# busses.net
KiCad netlist of a schematic drawn in EAGLE
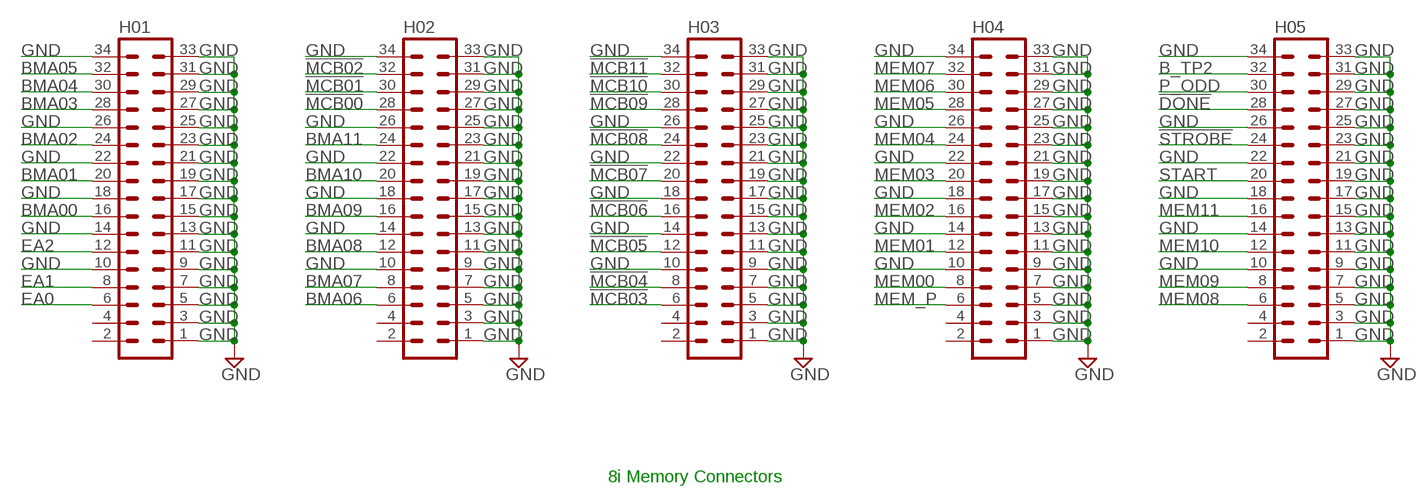
[diagram p0: schematic, sheet 1]
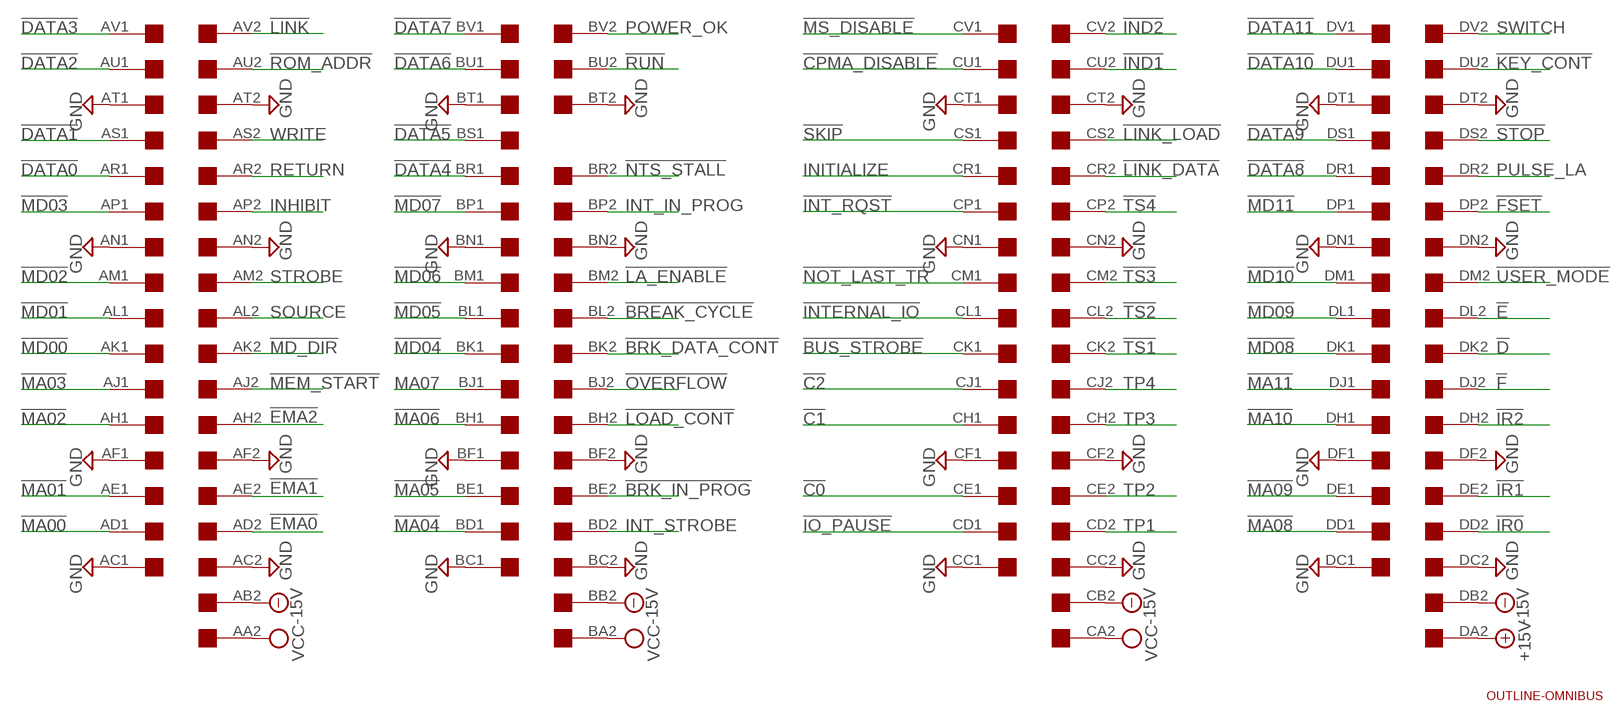
[diagram p1: schematic, sheet 2]
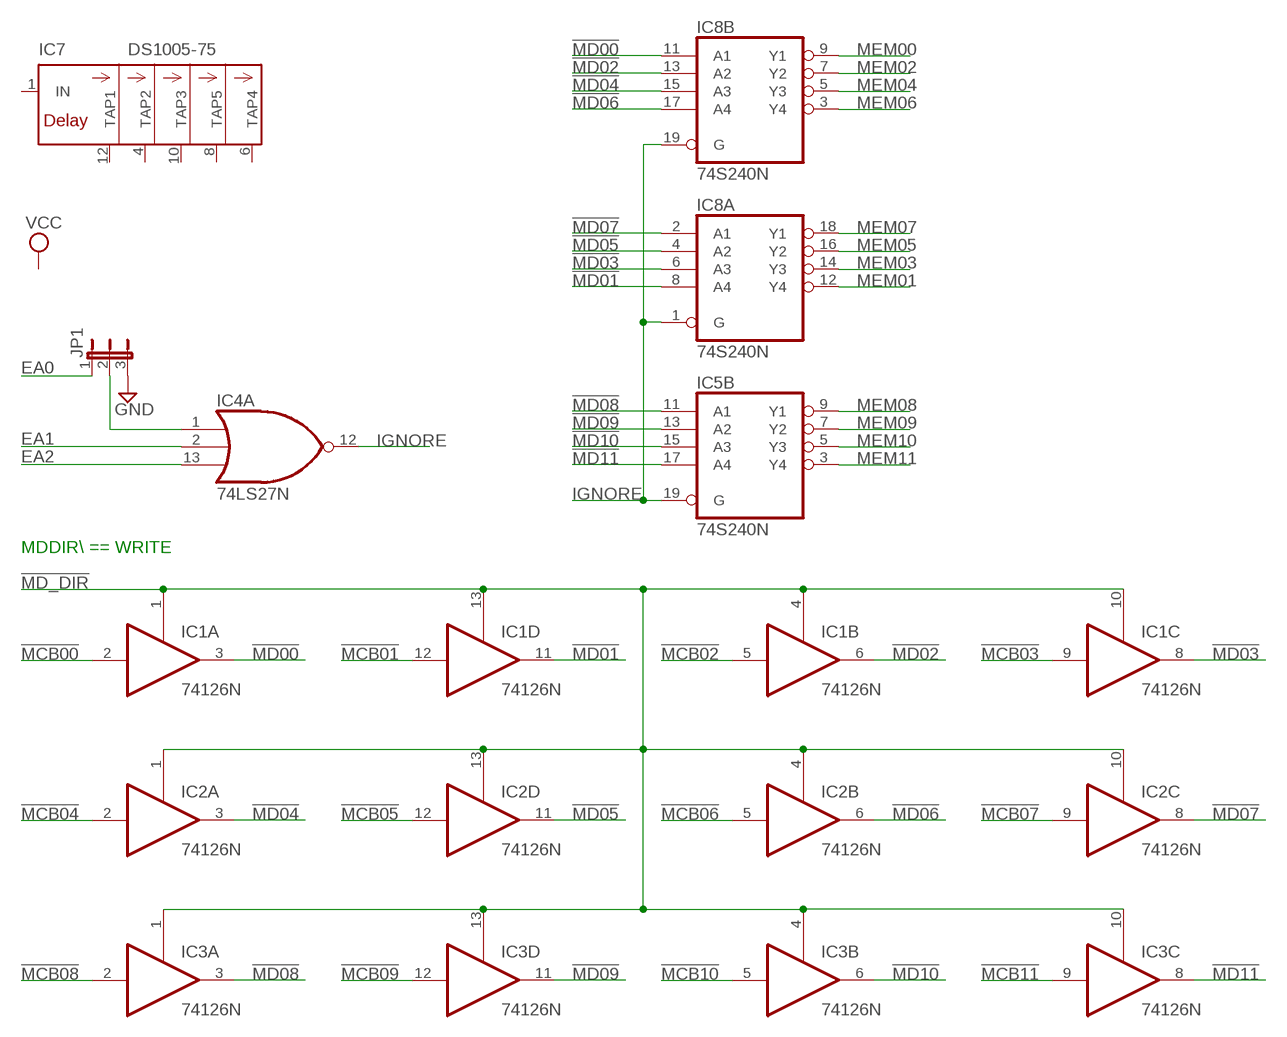
[diagram p2: schematic, sheet 3]
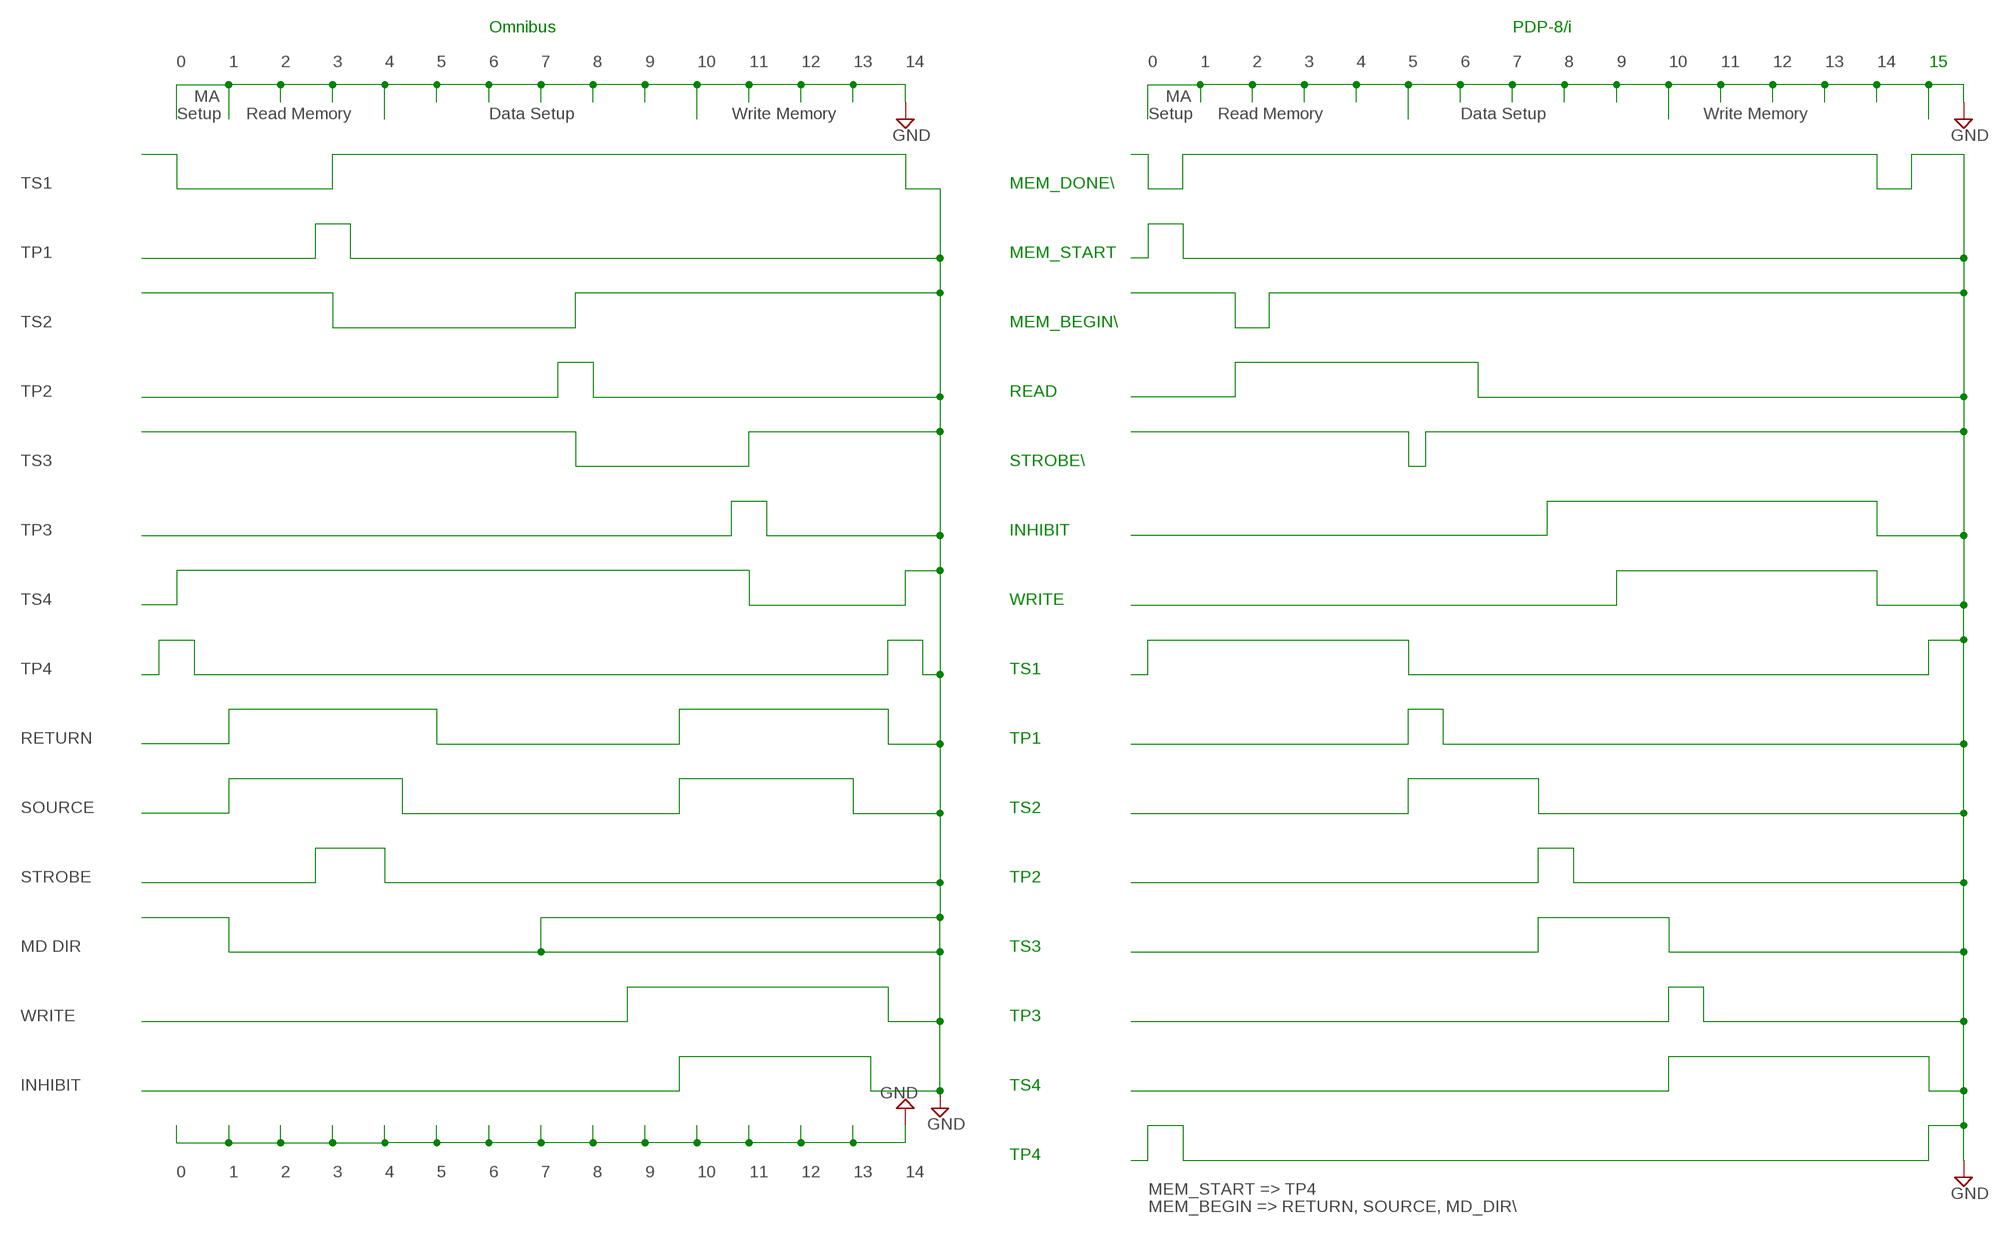
[diagram p3: schematic, sheet 4]

(export (version "E")
  (design (tool "Eeschema 10.0.6"))
  (components
    (comp (ref "U$1")
      (value "OUTLINE-OMNIBUS")
      (footprint "eagle-import:OMNIBUS")
      (libsource (lib "eagle-import") (part "OUTLINE-OMNIBUS"))
    )
    (comp (ref "U$2")
      (value "QUAD")
      (footprint "eagle-import:EDGE-CON8")
      (libsource (lib "eagle-import") (part "QUAD"))
    )
    (comp (ref "IC1")
      (value "74126N")
      (footprint "eagle-import:DIL14")
      (libsource (lib "eagle-import") (part "74126N"))
    )
    (comp (ref "IC2")
      (value "74126N")
      (footprint "eagle-import:DIL14")
      (libsource (lib "eagle-import") (part "74126N"))
    )
    (comp (ref "IC3")
      (value "74126N")
      (footprint "eagle-import:DIL14")
      (libsource (lib "eagle-import") (part "74126N"))
    )
    (comp (ref "IC4")
      (value "74LS27N")
      (footprint "eagle-import:DIL14")
      (libsource (lib "eagle-import") (part "7427NLS"))
    )
    (comp (ref "IC5")
      (value "74S240N")
      (footprint "eagle-import:DIL20")
      (libsource (lib "eagle-import") (part "74240NS"))
    )
    (comp (ref "IC7")
      (value "DS1005-75")
      (footprint "eagle-import:DIL14")
      (libsource (lib "eagle-import") (part "MXD1000P"))
    )
    (comp (ref "IC8")
      (value "74S240N")
      (footprint "eagle-import:DIL20")
      (libsource (lib "eagle-import") (part "74240NS"))
    )
    (comp (ref "JP1")
      (value "JP2E")
      (footprint "eagle-import:JP2")
      (libsource (lib "eagle-import") (part "JP2E"))
    )
    (comp (ref "H01")
      (value "MA17-2")
      (footprint "eagle-import:MA17-2")
      (libsource (lib "eagle-import") (part "MA17-2"))
    )
    (comp (ref "H02")
      (value "MA17-2")
      (footprint "eagle-import:MA17-2")
      (libsource (lib "eagle-import") (part "MA17-2"))
    )
    (comp (ref "H03")
      (value "MA17-2")
      (footprint "eagle-import:MA17-2")
      (libsource (lib "eagle-import") (part "MA17-2"))
    )
    (comp (ref "H04")
      (value "MA17-2")
      (footprint "eagle-import:MA17-2")
      (libsource (lib "eagle-import") (part "MA17-2"))
    )
    (comp (ref "H05")
      (value "MA17-2")
      (footprint "eagle-import:MA17-2")
      (libsource (lib "eagle-import") (part "MA17-2"))
    )
  )
  (nets
    (net (code "1") (name "+15V") (class "Default")
      (node (ref "U$2") (pin "DA2") (pinfunction "1_DA2") (pintype "bidirectional"))
    )
    (net (code "2") (name "-15V") (class "Default")
      (node (ref "U$2") (pin "AB2") (pinfunction "1_AB2") (pintype "bidirectional"))
      (node (ref "U$2") (pin "BB2") (pinfunction "1_BB2") (pintype "bidirectional"))
      (node (ref "U$2") (pin "CB2") (pinfunction "1_CB2") (pintype "bidirectional"))
      (node (ref "U$2") (pin "DB2") (pinfunction "1_DB2") (pintype "bidirectional"))
    )
    (net (code "3") (name "BMA00") (class "Default")
      (node (ref "H01") (pin "16") (pinfunction "16_16") (pintype "passive"))
    )
    (net (code "4") (name "BMA01") (class "Default")
      (node (ref "H01") (pin "20") (pinfunction "20_20") (pintype "passive"))
    )
    (net (code "5") (name "BMA02") (class "Default")
      (node (ref "H01") (pin "24") (pinfunction "24_24") (pintype "passive"))
    )
    (net (code "6") (name "BMA03") (class "Default")
      (node (ref "H01") (pin "28") (pinfunction "28_28") (pintype "passive"))
    )
    (net (code "7") (name "BMA04") (class "Default")
      (node (ref "H01") (pin "30") (pinfunction "30_30") (pintype "passive"))
    )
    (net (code "8") (name "BMA05") (class "Default")
      (node (ref "H01") (pin "32") (pinfunction "32_32") (pintype "passive"))
    )
    (net (code "9") (name "BMA06") (class "Default")
      (node (ref "H02") (pin "6") (pinfunction "6_6") (pintype "passive"))
    )
    (net (code "10") (name "BMA07") (class "Default")
      (node (ref "H02") (pin "8") (pinfunction "8_8") (pintype "passive"))
    )
    (net (code "11") (name "BMA08") (class "Default")
      (node (ref "H02") (pin "12") (pinfunction "12_12") (pintype "passive"))
    )
    (net (code "12") (name "BMA09") (class "Default")
      (node (ref "H02") (pin "16") (pinfunction "16_16") (pintype "passive"))
    )
    (net (code "13") (name "BMA10") (class "Default")
      (node (ref "H02") (pin "20") (pinfunction "20_20") (pintype "passive"))
    )
    (net (code "14") (name "BMA11") (class "Default")
      (node (ref "H02") (pin "24") (pinfunction "24_24") (pintype "passive"))
    )
    (net (code "15") (name "B_TP2") (class "Default")
      (node (ref "H05") (pin "32") (pinfunction "32_32") (pintype "passive"))
    )
    (net (code "16") (name "EA0") (class "Default")
      (node (ref "H01") (pin "6") (pinfunction "6_6") (pintype "passive"))
      (node (ref "JP1") (pin "1") (pinfunction "1_1") (pintype "passive"))
    )
    (net (code "17") (name "EA1") (class "Default")
      (node (ref "H01") (pin "8") (pinfunction "8_8") (pintype "passive"))
      (node (ref "IC4") (pin "2") (pinfunction "I1_2") (pintype "input"))
    )
    (net (code "18") (name "EA2") (class "Default")
      (node (ref "H01") (pin "12") (pinfunction "12_12") (pintype "passive"))
      (node (ref "IC4") (pin "13") (pinfunction "I2_13") (pintype "input"))
    )
    (net (code "19") (name "GND") (class "Default")
      (node (ref "H01") (pin "1") (pinfunction "1_1") (pintype "passive"))
      (node (ref "H01") (pin "10") (pinfunction "10_10") (pintype "passive"))
      (node (ref "H01") (pin "11") (pinfunction "11_11") (pintype "passive"))
      (node (ref "H01") (pin "13") (pinfunction "13_13") (pintype "passive"))
      (node (ref "H01") (pin "14") (pinfunction "14_14") (pintype "passive"))
      (node (ref "H01") (pin "15") (pinfunction "15_15") (pintype "passive"))
      (node (ref "H01") (pin "17") (pinfunction "17_17") (pintype "passive"))
      (node (ref "H01") (pin "18") (pinfunction "18_18") (pintype "passive"))
      (node (ref "H01") (pin "19") (pinfunction "19_19") (pintype "passive"))
      (node (ref "H01") (pin "21") (pinfunction "21_21") (pintype "passive"))
      (node (ref "H01") (pin "22") (pinfunction "22_22") (pintype "passive"))
      (node (ref "H01") (pin "23") (pinfunction "23_23") (pintype "passive"))
      (node (ref "H01") (pin "25") (pinfunction "25_25") (pintype "passive"))
      (node (ref "H01") (pin "26") (pinfunction "26_26") (pintype "passive"))
      (node (ref "H01") (pin "27") (pinfunction "27_27") (pintype "passive"))
      (node (ref "H01") (pin "29") (pinfunction "29_29") (pintype "passive"))
      (node (ref "H01") (pin "3") (pinfunction "3_3") (pintype "passive"))
      (node (ref "H01") (pin "31") (pinfunction "31_31") (pintype "passive"))
      (node (ref "H01") (pin "33") (pinfunction "33_33") (pintype "passive"))
      (node (ref "H01") (pin "34") (pinfunction "34_34") (pintype "passive"))
      (node (ref "H01") (pin "5") (pinfunction "5_5") (pintype "passive"))
      (node (ref "H01") (pin "7") (pinfunction "7_7") (pintype "passive"))
      (node (ref "H01") (pin "9") (pinfunction "9_9") (pintype "passive"))
      (node (ref "H02") (pin "1") (pinfunction "1_1") (pintype "passive"))
      (node (ref "H02") (pin "10") (pinfunction "10_10") (pintype "passive"))
      (node (ref "H02") (pin "11") (pinfunction "11_11") (pintype "passive"))
      (node (ref "H02") (pin "13") (pinfunction "13_13") (pintype "passive"))
      (node (ref "H02") (pin "14") (pinfunction "14_14") (pintype "passive"))
      (node (ref "H02") (pin "15") (pinfunction "15_15") (pintype "passive"))
      (node (ref "H02") (pin "17") (pinfunction "17_17") (pintype "passive"))
      (node (ref "H02") (pin "18") (pinfunction "18_18") (pintype "passive"))
      (node (ref "H02") (pin "19") (pinfunction "19_19") (pintype "passive"))
      (node (ref "H02") (pin "21") (pinfunction "21_21") (pintype "passive"))
      (node (ref "H02") (pin "22") (pinfunction "22_22") (pintype "passive"))
      (node (ref "H02") (pin "23") (pinfunction "23_23") (pintype "passive"))
      (node (ref "H02") (pin "25") (pinfunction "25_25") (pintype "passive"))
      (node (ref "H02") (pin "26") (pinfunction "26_26") (pintype "passive"))
      (node (ref "H02") (pin "27") (pinfunction "27_27") (pintype "passive"))
      (node (ref "H02") (pin "29") (pinfunction "29_29") (pintype "passive"))
      (node (ref "H02") (pin "3") (pinfunction "3_3") (pintype "passive"))
      (node (ref "H02") (pin "31") (pinfunction "31_31") (pintype "passive"))
      (node (ref "H02") (pin "33") (pinfunction "33_33") (pintype "passive"))
      (node (ref "H02") (pin "34") (pinfunction "34_34") (pintype "passive"))
      (node (ref "H02") (pin "5") (pinfunction "5_5") (pintype "passive"))
      (node (ref "H02") (pin "7") (pinfunction "7_7") (pintype "passive"))
      (node (ref "H02") (pin "9") (pinfunction "9_9") (pintype "passive"))
      (node (ref "H03") (pin "1") (pinfunction "1_1") (pintype "passive"))
      (node (ref "H03") (pin "10") (pinfunction "10_10") (pintype "passive"))
      (node (ref "H03") (pin "11") (pinfunction "11_11") (pintype "passive"))
      (node (ref "H03") (pin "13") (pinfunction "13_13") (pintype "passive"))
      (node (ref "H03") (pin "14") (pinfunction "14_14") (pintype "passive"))
      (node (ref "H03") (pin "15") (pinfunction "15_15") (pintype "passive"))
      (node (ref "H03") (pin "17") (pinfunction "17_17") (pintype "passive"))
      (node (ref "H03") (pin "18") (pinfunction "18_18") (pintype "passive"))
      (node (ref "H03") (pin "19") (pinfunction "19_19") (pintype "passive"))
      (node (ref "H03") (pin "21") (pinfunction "21_21") (pintype "passive"))
      (node (ref "H03") (pin "22") (pinfunction "22_22") (pintype "passive"))
      (node (ref "H03") (pin "23") (pinfunction "23_23") (pintype "passive"))
      (node (ref "H03") (pin "25") (pinfunction "25_25") (pintype "passive"))
      (node (ref "H03") (pin "26") (pinfunction "26_26") (pintype "passive"))
      (node (ref "H03") (pin "27") (pinfunction "27_27") (pintype "passive"))
      (node (ref "H03") (pin "29") (pinfunction "29_29") (pintype "passive"))
      (node (ref "H03") (pin "3") (pinfunction "3_3") (pintype "passive"))
      (node (ref "H03") (pin "31") (pinfunction "31_31") (pintype "passive"))
      (node (ref "H03") (pin "33") (pinfunction "33_33") (pintype "passive"))
      (node (ref "H03") (pin "34") (pinfunction "34_34") (pintype "passive"))
      (node (ref "H03") (pin "5") (pinfunction "5_5") (pintype "passive"))
      (node (ref "H03") (pin "7") (pinfunction "7_7") (pintype "passive"))
      (node (ref "H03") (pin "9") (pinfunction "9_9") (pintype "passive"))
      (node (ref "H04") (pin "1") (pinfunction "1_1") (pintype "passive"))
      (node (ref "H04") (pin "10") (pinfunction "10_10") (pintype "passive"))
      (node (ref "H04") (pin "11") (pinfunction "11_11") (pintype "passive"))
      (node (ref "H04") (pin "13") (pinfunction "13_13") (pintype "passive"))
      (node (ref "H04") (pin "14") (pinfunction "14_14") (pintype "passive"))
      (node (ref "H04") (pin "15") (pinfunction "15_15") (pintype "passive"))
      (node (ref "H04") (pin "17") (pinfunction "17_17") (pintype "passive"))
      (node (ref "H04") (pin "18") (pinfunction "18_18") (pintype "passive"))
      (node (ref "H04") (pin "19") (pinfunction "19_19") (pintype "passive"))
      (node (ref "H04") (pin "21") (pinfunction "21_21") (pintype "passive"))
      (node (ref "H04") (pin "22") (pinfunction "22_22") (pintype "passive"))
      (node (ref "H04") (pin "23") (pinfunction "23_23") (pintype "passive"))
      (node (ref "H04") (pin "25") (pinfunction "25_25") (pintype "passive"))
      (node (ref "H04") (pin "26") (pinfunction "26_26") (pintype "passive"))
      (node (ref "H04") (pin "27") (pinfunction "27_27") (pintype "passive"))
      (node (ref "H04") (pin "29") (pinfunction "29_29") (pintype "passive"))
      (node (ref "H04") (pin "3") (pinfunction "3_3") (pintype "passive"))
      (node (ref "H04") (pin "31") (pinfunction "31_31") (pintype "passive"))
      (node (ref "H04") (pin "33") (pinfunction "33_33") (pintype "passive"))
      (node (ref "H04") (pin "34") (pinfunction "34_34") (pintype "passive"))
      (node (ref "H04") (pin "5") (pinfunction "5_5") (pintype "passive"))
      (node (ref "H04") (pin "7") (pinfunction "7_7") (pintype "passive"))
      (node (ref "H04") (pin "9") (pinfunction "9_9") (pintype "passive"))
      (node (ref "H05") (pin "1") (pinfunction "1_1") (pintype "passive"))
      (node (ref "H05") (pin "10") (pinfunction "10_10") (pintype "passive"))
      (node (ref "H05") (pin "11") (pinfunction "11_11") (pintype "passive"))
      (node (ref "H05") (pin "13") (pinfunction "13_13") (pintype "passive"))
      (node (ref "H05") (pin "14") (pinfunction "14_14") (pintype "passive"))
      (node (ref "H05") (pin "15") (pinfunction "15_15") (pintype "passive"))
      (node (ref "H05") (pin "17") (pinfunction "17_17") (pintype "passive"))
      (node (ref "H05") (pin "18") (pinfunction "18_18") (pintype "passive"))
      (node (ref "H05") (pin "19") (pinfunction "19_19") (pintype "passive"))
      (node (ref "H05") (pin "21") (pinfunction "21_21") (pintype "passive"))
      (node (ref "H05") (pin "22") (pinfunction "22_22") (pintype "passive"))
      (node (ref "H05") (pin "23") (pinfunction "23_23") (pintype "passive"))
      (node (ref "H05") (pin "25") (pinfunction "25_25") (pintype "passive"))
      (node (ref "H05") (pin "26") (pinfunction "26_26") (pintype "passive"))
      (node (ref "H05") (pin "27") (pinfunction "27_27") (pintype "passive"))
      (node (ref "H05") (pin "29") (pinfunction "29_29") (pintype "passive"))
      (node (ref "H05") (pin "3") (pinfunction "3_3") (pintype "passive"))
      (node (ref "H05") (pin "31") (pinfunction "31_31") (pintype "passive"))
      (node (ref "H05") (pin "33") (pinfunction "33_33") (pintype "passive"))
      (node (ref "H05") (pin "34") (pinfunction "34_34") (pintype "passive"))
      (node (ref "H05") (pin "5") (pinfunction "5_5") (pintype "passive"))
      (node (ref "H05") (pin "7") (pinfunction "7_7") (pintype "passive"))
      (node (ref "H05") (pin "9") (pinfunction "9_9") (pintype "passive"))
      (node (ref "JP1") (pin "3") (pinfunction "3_3") (pintype "passive"))
      (node (ref "U$2") (pin "AC1") (pinfunction "1_AC1") (pintype "bidirectional"))
      (node (ref "U$2") (pin "AC2") (pinfunction "1_AC2") (pintype "bidirectional"))
      (node (ref "U$2") (pin "AF1") (pinfunction "1_AF1") (pintype "bidirectional"))
      (node (ref "U$2") (pin "AF2") (pinfunction "1_AF2") (pintype "bidirectional"))
      (node (ref "U$2") (pin "AN1") (pinfunction "1_AN1") (pintype "bidirectional"))
      (node (ref "U$2") (pin "AN2") (pinfunction "1_AN2") (pintype "bidirectional"))
      (node (ref "U$2") (pin "AT1") (pinfunction "1_AT1") (pintype "bidirectional"))
      (node (ref "U$2") (pin "AT2") (pinfunction "1_AT2") (pintype "bidirectional"))
      (node (ref "U$2") (pin "BC1") (pinfunction "1_BC1") (pintype "bidirectional"))
      (node (ref "U$2") (pin "BC2") (pinfunction "1_BC2") (pintype "bidirectional"))
      (node (ref "U$2") (pin "BF1") (pinfunction "1_BF1") (pintype "bidirectional"))
      (node (ref "U$2") (pin "BF2") (pinfunction "1_BF2") (pintype "bidirectional"))
      (node (ref "U$2") (pin "BN1") (pinfunction "1_BN1") (pintype "bidirectional"))
      (node (ref "U$2") (pin "BN2") (pinfunction "1_BN2") (pintype "bidirectional"))
      (node (ref "U$2") (pin "BT1") (pinfunction "1_BT1") (pintype "bidirectional"))
      (node (ref "U$2") (pin "BT2") (pinfunction "1_BT2") (pintype "bidirectional"))
      (node (ref "U$2") (pin "CC1") (pinfunction "1_CC1") (pintype "bidirectional"))
      (node (ref "U$2") (pin "CC2") (pinfunction "1_CC2") (pintype "bidirectional"))
      (node (ref "U$2") (pin "CF1") (pinfunction "1_CF1") (pintype "bidirectional"))
      (node (ref "U$2") (pin "CF2") (pinfunction "1_CF2") (pintype "bidirectional"))
      (node (ref "U$2") (pin "CN1") (pinfunction "1_CN1") (pintype "bidirectional"))
      (node (ref "U$2") (pin "CN2") (pinfunction "1_CN2") (pintype "bidirectional"))
      (node (ref "U$2") (pin "CT1") (pinfunction "1_CT1") (pintype "bidirectional"))
      (node (ref "U$2") (pin "CT2") (pinfunction "1_CT2") (pintype "bidirectional"))
      (node (ref "U$2") (pin "DC1") (pinfunction "1_DC1") (pintype "bidirectional"))
      (node (ref "U$2") (pin "DC2") (pinfunction "1_DC2") (pintype "bidirectional"))
      (node (ref "U$2") (pin "DF1") (pinfunction "1_DF1") (pintype "bidirectional"))
      (node (ref "U$2") (pin "DF2") (pinfunction "1_DF2") (pintype "bidirectional"))
      (node (ref "U$2") (pin "DN1") (pinfunction "1_DN1") (pintype "bidirectional"))
      (node (ref "U$2") (pin "DN2") (pinfunction "1_DN2") (pintype "bidirectional"))
      (node (ref "U$2") (pin "DT1") (pinfunction "1_DT1") (pintype "bidirectional"))
      (node (ref "U$2") (pin "DT2") (pinfunction "1_DT2") (pintype "bidirectional"))
    )
    (net (code "20") (name "IGNORE") (class "Default")
      (node (ref "IC4") (pin "12") (pinfunction "O_12") (pintype "output"))
      (node (ref "IC5") (pin "19") (pinfunction "G_19") (pintype "input"))
      (node (ref "IC8") (pin "1") (pinfunction "G_1") (pintype "input"))
      (node (ref "IC8") (pin "19") (pinfunction "G_19") (pintype "input"))
    )
    (net (code "21") (name "INHIBIT") (class "Default")
      (node (ref "U$2") (pin "AP2") (pinfunction "1_AP2") (pintype "bidirectional"))
    )
    (net (code "22") (name "INITIALIZE") (class "Default")
      (node (ref "U$2") (pin "CR1") (pinfunction "1_CR1") (pintype "bidirectional"))
    )
    (net (code "23") (name "INT_IN_PROG") (class "Default")
      (node (ref "U$2") (pin "BP2") (pinfunction "1_BP2") (pintype "bidirectional"))
    )
    (net (code "24") (name "INT_STROBE") (class "Default")
      (node (ref "U$2") (pin "BD2") (pinfunction "1_BD2") (pintype "bidirectional"))
    )
    (net (code "25") (name "MA07") (class "Default")
      (node (ref "U$2") (pin "BJ1") (pinfunction "1_BJ1") (pintype "bidirectional"))
    )
    (net (code "26") (name "MEM00") (class "Default")
      (node (ref "H04") (pin "8") (pinfunction "8_8") (pintype "passive"))
      (node (ref "IC8") (pin "9") (pinfunction "Y1_9") (pintype "tri_state"))
    )
    (net (code "27") (name "MEM01") (class "Default")
      (node (ref "H04") (pin "12") (pinfunction "12_12") (pintype "passive"))
      (node (ref "IC8") (pin "12") (pinfunction "Y4_12") (pintype "tri_state"))
    )
    (net (code "28") (name "MEM02") (class "Default")
      (node (ref "H04") (pin "16") (pinfunction "16_16") (pintype "passive"))
      (node (ref "IC8") (pin "7") (pinfunction "Y2_7") (pintype "tri_state"))
    )
    (net (code "29") (name "MEM03") (class "Default")
      (node (ref "H04") (pin "20") (pinfunction "20_20") (pintype "passive"))
      (node (ref "IC8") (pin "14") (pinfunction "Y3_14") (pintype "tri_state"))
    )
    (net (code "30") (name "MEM04") (class "Default")
      (node (ref "H04") (pin "24") (pinfunction "24_24") (pintype "passive"))
      (node (ref "IC8") (pin "5") (pinfunction "Y3_5") (pintype "tri_state"))
    )
    (net (code "31") (name "MEM05") (class "Default")
      (node (ref "H04") (pin "28") (pinfunction "28_28") (pintype "passive"))
      (node (ref "IC8") (pin "16") (pinfunction "Y2_16") (pintype "tri_state"))
    )
    (net (code "32") (name "MEM06") (class "Default")
      (node (ref "H04") (pin "30") (pinfunction "30_30") (pintype "passive"))
      (node (ref "IC8") (pin "3") (pinfunction "Y4_3") (pintype "tri_state"))
    )
    (net (code "33") (name "MEM07") (class "Default")
      (node (ref "H04") (pin "32") (pinfunction "32_32") (pintype "passive"))
      (node (ref "IC8") (pin "18") (pinfunction "Y1_18") (pintype "tri_state"))
    )
    (net (code "34") (name "MEM08") (class "Default")
      (node (ref "H05") (pin "6") (pinfunction "6_6") (pintype "passive"))
      (node (ref "IC5") (pin "9") (pinfunction "Y1_9") (pintype "tri_state"))
    )
    (net (code "35") (name "MEM09") (class "Default")
      (node (ref "H05") (pin "8") (pinfunction "8_8") (pintype "passive"))
      (node (ref "IC5") (pin "7") (pinfunction "Y2_7") (pintype "tri_state"))
    )
    (net (code "36") (name "MEM10") (class "Default")
      (node (ref "H05") (pin "12") (pinfunction "12_12") (pintype "passive"))
      (node (ref "IC5") (pin "5") (pinfunction "Y3_5") (pintype "tri_state"))
    )
    (net (code "37") (name "MEM11") (class "Default")
      (node (ref "H05") (pin "16") (pinfunction "16_16") (pintype "passive"))
      (node (ref "IC5") (pin "3") (pinfunction "Y4_3") (pintype "tri_state"))
    )
    (net (code "38") (name "MEM_P") (class "Default")
      (node (ref "H04") (pin "6") (pinfunction "6_6") (pintype "passive"))
    )
    (net (code "39") (name "Net-(IC4A-I0)") (class "Default")
      (node (ref "IC4") (pin "1") (pinfunction "I0_1") (pintype "input"))
      (node (ref "JP1") (pin "2") (pinfunction "2_2") (pintype "passive"))
    )
    (net (code "40") (name "POWER_OK") (class "Default")
      (node (ref "U$2") (pin "BV2") (pinfunction "1_BV2") (pintype "bidirectional"))
    )
    (net (code "41") (name "PULSE_LA") (class "Default")
      (node (ref "U$2") (pin "DR2") (pinfunction "1_DR2") (pintype "bidirectional"))
    )
    (net (code "42") (name "P_ODD") (class "Default")
      (node (ref "H05") (pin "30") (pinfunction "30_30") (pintype "passive"))
    )
    (net (code "43") (name "RETURN") (class "Default")
      (node (ref "U$2") (pin "AR2") (pinfunction "1_AR2") (pintype "bidirectional"))
    )
    (net (code "44") (name "SOURCE") (class "Default")
      (node (ref "U$2") (pin "AL2") (pinfunction "1_AL2") (pintype "bidirectional"))
    )
    (net (code "45") (name "START") (class "Default")
      (node (ref "H05") (pin "20") (pinfunction "20_20") (pintype "passive"))
    )
    (net (code "46") (name "STROBE") (class "Default")
      (node (ref "U$2") (pin "AM2") (pinfunction "1_AM2") (pintype "bidirectional"))
    )
    (net (code "47") (name "SWITCH") (class "Default")
      (node (ref "U$2") (pin "DV2") (pinfunction "1_DV2") (pintype "bidirectional"))
    )
    (net (code "48") (name "TP1") (class "Default")
      (node (ref "U$2") (pin "CD2") (pinfunction "1_CD2") (pintype "bidirectional"))
    )
    (net (code "49") (name "TP2") (class "Default")
      (node (ref "U$2") (pin "CE2") (pinfunction "1_CE2") (pintype "bidirectional"))
    )
    (net (code "50") (name "TP3") (class "Default")
      (node (ref "U$2") (pin "CH2") (pinfunction "1_CH2") (pintype "bidirectional"))
    )
    (net (code "51") (name "TP4") (class "Default")
      (node (ref "U$2") (pin "CJ2") (pinfunction "1_CJ2") (pintype "bidirectional"))
    )
    (net (code "52") (name "VCC") (class "Default")
      (node (ref "U$2") (pin "AA2") (pinfunction "1_AA2") (pintype "bidirectional"))
      (node (ref "U$2") (pin "BA2") (pinfunction "1_BA2") (pintype "bidirectional"))
      (node (ref "U$2") (pin "CA2") (pinfunction "1_CA2") (pintype "bidirectional"))
    )
    (net (code "53") (name "WRITE") (class "Default")
      (node (ref "U$2") (pin "AS2") (pinfunction "1_AS2") (pintype "bidirectional"))
    )
    (net (code "54") (name "unconnected-(H01-Pad2)") (class "Default")
      (node (ref "H01") (pin "2") (pinfunction "2_2") (pintype "passive"))
    )
    (net (code "55") (name "unconnected-(H01-Pad4)") (class "Default")
      (node (ref "H01") (pin "4") (pinfunction "4_4") (pintype "passive"))
    )
    (net (code "56") (name "unconnected-(H02-Pad2)") (class "Default")
      (node (ref "H02") (pin "2") (pinfunction "2_2") (pintype "passive"))
    )
    (net (code "57") (name "unconnected-(H02-Pad4)") (class "Default")
      (node (ref "H02") (pin "4") (pinfunction "4_4") (pintype "passive"))
    )
    (net (code "58") (name "unconnected-(H03-Pad2)") (class "Default")
      (node (ref "H03") (pin "2") (pinfunction "2_2") (pintype "passive"))
    )
    (net (code "59") (name "unconnected-(H03-Pad4)") (class "Default")
      (node (ref "H03") (pin "4") (pinfunction "4_4") (pintype "passive"))
    )
    (net (code "60") (name "unconnected-(H04-Pad2)") (class "Default")
      (node (ref "H04") (pin "2") (pinfunction "2_2") (pintype "passive"))
    )
    (net (code "61") (name "unconnected-(H04-Pad4)") (class "Default")
      (node (ref "H04") (pin "4") (pinfunction "4_4") (pintype "passive"))
    )
    (net (code "62") (name "unconnected-(H05-Pad2)") (class "Default")
      (node (ref "H05") (pin "2") (pinfunction "2_2") (pintype "passive"))
    )
    (net (code "63") (name "unconnected-(H05-Pad4)") (class "Default")
      (node (ref "H05") (pin "4") (pinfunction "4_4") (pintype "passive"))
    )
    (net (code "64") (name "unconnected-(IC7G-IN-Pad1)") (class "Default")
      (node (ref "IC7") (pin "1") (pinfunction "IN_1") (pintype "input"))
    )
    (net (code "65") (name "unconnected-(IC7G-TAP1-Pad12)") (class "Default")
      (node (ref "IC7") (pin "12") (pinfunction "TAP1_12") (pintype "output"))
    )
    (net (code "66") (name "unconnected-(IC7G-TAP2-Pad4)") (class "Default")
      (node (ref "IC7") (pin "4") (pinfunction "TAP2_4") (pintype "output"))
    )
    (net (code "67") (name "unconnected-(IC7G-TAP3-Pad10)") (class "Default")
      (node (ref "IC7") (pin "10") (pinfunction "TAP3_10") (pintype "output"))
    )
    (net (code "68") (name "unconnected-(IC7G-TAP4-Pad6)") (class "Default")
      (node (ref "IC7") (pin "6") (pinfunction "TAP4_6") (pintype "output"))
    )
    (net (code "69") (name "unconnected-(IC7G-TAP5-Pad8)") (class "Default")
      (node (ref "IC7") (pin "8") (pinfunction "TAP5_8") (pintype "output"))
    )
    (net (code "70") (name "~{BREAK_CYCLE}") (class "Default")
      (node (ref "U$2") (pin "BL2") (pinfunction "1_BL2") (pintype "bidirectional"))
    )
    (net (code "71") (name "~{BRK_DATA_CONT}") (class "Default")
      (node (ref "U$2") (pin "BK2") (pinfunction "1_BK2") (pintype "bidirectional"))
    )
    (net (code "72") (name "~{BRK_IN_PROG}") (class "Default")
      (node (ref "U$2") (pin "BE2") (pinfunction "1_BE2") (pintype "bidirectional"))
    )
    (net (code "73") (name "~{BUS_STROBE}") (class "Default")
      (node (ref "U$2") (pin "CK1") (pinfunction "1_CK1") (pintype "bidirectional"))
    )
    (net (code "74") (name "~{C0}") (class "Default")
      (node (ref "U$2") (pin "CE1") (pinfunction "1_CE1") (pintype "bidirectional"))
    )
    (net (code "75") (name "~{C1}") (class "Default")
      (node (ref "U$2") (pin "CH1") (pinfunction "1_CH1") (pintype "bidirectional"))
    )
    (net (code "76") (name "~{C2}") (class "Default")
      (node (ref "U$2") (pin "CJ1") (pinfunction "1_CJ1") (pintype "bidirectional"))
    )
    (net (code "77") (name "~{CPMA_DISABLE}") (class "Default")
      (node (ref "U$2") (pin "CU1") (pinfunction "1_CU1") (pintype "bidirectional"))
    )
    (net (code "78") (name "~{DATA0}") (class "Default")
      (node (ref "U$2") (pin "AR1") (pinfunction "1_AR1") (pintype "bidirectional"))
    )
    (net (code "79") (name "~{DATA1}") (class "Default")
      (node (ref "U$2") (pin "AS1") (pinfunction "1_AS1") (pintype "bidirectional"))
    )
    (net (code "80") (name "~{DATA2}") (class "Default")
      (node (ref "U$2") (pin "AU1") (pinfunction "1_AU1") (pintype "bidirectional"))
    )
    (net (code "81") (name "~{DATA3}") (class "Default")
      (node (ref "U$2") (pin "AV1") (pinfunction "1_AV1") (pintype "bidirectional"))
    )
    (net (code "82") (name "~{DATA4}") (class "Default")
      (node (ref "U$2") (pin "BR1") (pinfunction "1_BR1") (pintype "bidirectional"))
    )
    (net (code "83") (name "~{DATA5}") (class "Default")
      (node (ref "U$2") (pin "BS1") (pinfunction "1_BS1") (pintype "bidirectional"))
    )
    (net (code "84") (name "~{DATA6}") (class "Default")
      (node (ref "U$2") (pin "BU1") (pinfunction "1_BU1") (pintype "bidirectional"))
    )
    (net (code "85") (name "~{DATA7}") (class "Default")
      (node (ref "U$2") (pin "BV1") (pinfunction "1_BV1") (pintype "bidirectional"))
    )
    (net (code "86") (name "~{DATA8}") (class "Default")
      (node (ref "U$2") (pin "DR1") (pinfunction "1_DR1") (pintype "bidirectional"))
    )
    (net (code "87") (name "~{DATA9}") (class "Default")
      (node (ref "U$2") (pin "DS1") (pinfunction "1_DS1") (pintype "bidirectional"))
    )
    (net (code "88") (name "~{DATA10}") (class "Default")
      (node (ref "U$2") (pin "DU1") (pinfunction "1_DU1") (pintype "bidirectional"))
    )
    (net (code "89") (name "~{DATA11}") (class "Default")
      (node (ref "U$2") (pin "DV1") (pinfunction "1_DV1") (pintype "bidirectional"))
    )
    (net (code "90") (name "~{DONE}") (class "Default")
      (node (ref "H05") (pin "28") (pinfunction "28_28") (pintype "passive"))
    )
    (net (code "91") (name "~{D}") (class "Default")
      (node (ref "U$2") (pin "DK2") (pinfunction "1_DK2") (pintype "bidirectional"))
    )
    (net (code "92") (name "~{EMA0}") (class "Default")
      (node (ref "U$2") (pin "AD2") (pinfunction "1_AD2") (pintype "bidirectional"))
    )
    (net (code "93") (name "~{EMA1}") (class "Default")
      (node (ref "U$2") (pin "AE2") (pinfunction "1_AE2") (pintype "bidirectional"))
    )
    (net (code "94") (name "~{EMA2}") (class "Default")
      (node (ref "U$2") (pin "AH2") (pinfunction "1_AH2") (pintype "bidirectional"))
    )
    (net (code "95") (name "~{E}") (class "Default")
      (node (ref "U$2") (pin "DL2") (pinfunction "1_DL2") (pintype "bidirectional"))
    )
    (net (code "96") (name "~{FSET}") (class "Default")
      (node (ref "U$2") (pin "DP2") (pinfunction "1_DP2") (pintype "bidirectional"))
    )
    (net (code "97") (name "~{F}") (class "Default")
      (node (ref "U$2") (pin "DJ2") (pinfunction "1_DJ2") (pintype "bidirectional"))
    )
    (net (code "98") (name "~{IND1}") (class "Default")
      (node (ref "U$2") (pin "CU2") (pinfunction "1_CU2") (pintype "bidirectional"))
    )
    (net (code "99") (name "~{IND2}") (class "Default")
      (node (ref "U$2") (pin "CV2") (pinfunction "1_CV2") (pintype "bidirectional"))
    )
    (net (code "100") (name "~{INTERNAL_IO}") (class "Default")
      (node (ref "U$2") (pin "CL1") (pinfunction "1_CL1") (pintype "bidirectional"))
    )
    (net (code "101") (name "~{INT_RQST}") (class "Default")
      (node (ref "U$2") (pin "CP1") (pinfunction "1_CP1") (pintype "bidirectional"))
    )
    (net (code "102") (name "~{IO_PAUSE}") (class "Default")
      (node (ref "U$2") (pin "CD1") (pinfunction "1_CD1") (pintype "bidirectional"))
    )
    (net (code "103") (name "~{IR0}") (class "Default")
      (node (ref "U$2") (pin "DD2") (pinfunction "1_DD2") (pintype "bidirectional"))
    )
    (net (code "104") (name "~{IR1}") (class "Default")
      (node (ref "U$2") (pin "DE2") (pinfunction "1_DE2") (pintype "bidirectional"))
    )
    (net (code "105") (name "~{IR2}") (class "Default")
      (node (ref "U$2") (pin "DH2") (pinfunction "1_DH2") (pintype "bidirectional"))
    )
    (net (code "106") (name "~{KEY_CONT}") (class "Default")
      (node (ref "U$2") (pin "DU2") (pinfunction "1_DU2") (pintype "bidirectional"))
    )
    (net (code "107") (name "~{LA_ENABLE}") (class "Default")
      (node (ref "U$2") (pin "BM2") (pinfunction "1_BM2") (pintype "bidirectional"))
    )
    (net (code "108") (name "~{LINK_DATA}") (class "Default")
      (node (ref "U$2") (pin "CR2") (pinfunction "1_CR2") (pintype "bidirectional"))
    )
    (net (code "109") (name "~{LINK_LOAD}") (class "Default")
      (node (ref "U$2") (pin "CS2") (pinfunction "1_CS2") (pintype "bidirectional"))
    )
    (net (code "110") (name "~{LINK}") (class "Default")
      (node (ref "U$2") (pin "AV2") (pinfunction "1_AV2") (pintype "bidirectional"))
    )
    (net (code "111") (name "~{LOAD_CONT}") (class "Default")
      (node (ref "U$2") (pin "BH2") (pinfunction "1_BH2") (pintype "bidirectional"))
    )
    (net (code "112") (name "~{MA00}") (class "Default")
      (node (ref "U$2") (pin "AD1") (pinfunction "1_AD1") (pintype "bidirectional"))
    )
    (net (code "113") (name "~{MA01}") (class "Default")
      (node (ref "U$2") (pin "AE1") (pinfunction "1_AE1") (pintype "bidirectional"))
    )
    (net (code "114") (name "~{MA02}") (class "Default")
      (node (ref "U$2") (pin "AH1") (pinfunction "1_AH1") (pintype "bidirectional"))
    )
    (net (code "115") (name "~{MA03}") (class "Default")
      (node (ref "U$2") (pin "AJ1") (pinfunction "1_AJ1") (pintype "bidirectional"))
    )
    (net (code "116") (name "~{MA04}") (class "Default")
      (node (ref "U$2") (pin "BD1") (pinfunction "1_BD1") (pintype "bidirectional"))
    )
    (net (code "117") (name "~{MA05}") (class "Default")
      (node (ref "U$2") (pin "BE1") (pinfunction "1_BE1") (pintype "bidirectional"))
    )
    (net (code "118") (name "~{MA06}") (class "Default")
      (node (ref "U$2") (pin "BH1") (pinfunction "1_BH1") (pintype "bidirectional"))
    )
    (net (code "119") (name "~{MA08}") (class "Default")
      (node (ref "U$2") (pin "DD1") (pinfunction "1_DD1") (pintype "bidirectional"))
    )
    (net (code "120") (name "~{MA09}") (class "Default")
      (node (ref "U$2") (pin "DE1") (pinfunction "1_DE1") (pintype "bidirectional"))
    )
    (net (code "121") (name "~{MA10}") (class "Default")
      (node (ref "U$2") (pin "DH1") (pinfunction "1_DH1") (pintype "bidirectional"))
    )
    (net (code "122") (name "~{MA11}") (class "Default")
      (node (ref "U$2") (pin "DJ1") (pinfunction "1_DJ1") (pintype "bidirectional"))
    )
    (net (code "123") (name "~{MCB00}") (class "Default")
      (node (ref "H02") (pin "28") (pinfunction "28_28") (pintype "passive"))
      (node (ref "IC1") (pin "2") (pinfunction "I_2") (pintype "input"))
    )
    (net (code "124") (name "~{MCB01}") (class "Default")
      (node (ref "H02") (pin "30") (pinfunction "30_30") (pintype "passive"))
      (node (ref "IC1") (pin "12") (pinfunction "I_12") (pintype "input"))
    )
    (net (code "125") (name "~{MCB02}") (class "Default")
      (node (ref "H02") (pin "32") (pinfunction "32_32") (pintype "passive"))
      (node (ref "IC1") (pin "5") (pinfunction "I_5") (pintype "input"))
    )
    (net (code "126") (name "~{MCB03}") (class "Default")
      (node (ref "H03") (pin "6") (pinfunction "6_6") (pintype "passive"))
      (node (ref "IC1") (pin "9") (pinfunction "I_9") (pintype "input"))
    )
    (net (code "127") (name "~{MCB04}") (class "Default")
      (node (ref "H03") (pin "8") (pinfunction "8_8") (pintype "passive"))
      (node (ref "IC2") (pin "2") (pinfunction "I_2") (pintype "input"))
    )
    (net (code "128") (name "~{MCB05}") (class "Default")
      (node (ref "H03") (pin "12") (pinfunction "12_12") (pintype "passive"))
      (node (ref "IC2") (pin "12") (pinfunction "I_12") (pintype "input"))
    )
    (net (code "129") (name "~{MCB06}") (class "Default")
      (node (ref "H03") (pin "16") (pinfunction "16_16") (pintype "passive"))
      (node (ref "IC2") (pin "5") (pinfunction "I_5") (pintype "input"))
    )
    (net (code "130") (name "~{MCB07}") (class "Default")
      (node (ref "H03") (pin "20") (pinfunction "20_20") (pintype "passive"))
      (node (ref "IC2") (pin "9") (pinfunction "I_9") (pintype "input"))
    )
    (net (code "131") (name "~{MCB08}") (class "Default")
      (node (ref "H03") (pin "24") (pinfunction "24_24") (pintype "passive"))
      (node (ref "IC3") (pin "2") (pinfunction "I_2") (pintype "input"))
    )
    (net (code "132") (name "~{MCB09}") (class "Default")
      (node (ref "H03") (pin "28") (pinfunction "28_28") (pintype "passive"))
      (node (ref "IC3") (pin "12") (pinfunction "I_12") (pintype "input"))
    )
    (net (code "133") (name "~{MCB10}") (class "Default")
      (node (ref "H03") (pin "30") (pinfunction "30_30") (pintype "passive"))
      (node (ref "IC3") (pin "5") (pinfunction "I_5") (pintype "input"))
    )
    (net (code "134") (name "~{MCB11}") (class "Default")
      (node (ref "H03") (pin "32") (pinfunction "32_32") (pintype "passive"))
      (node (ref "IC3") (pin "9") (pinfunction "I_9") (pintype "input"))
    )
    (net (code "135") (name "~{MD00}") (class "Default")
      (node (ref "IC1") (pin "3") (pinfunction "O_3") (pintype "output"))
      (node (ref "IC8") (pin "11") (pinfunction "A1_11") (pintype "input"))
      (node (ref "U$2") (pin "AK1") (pinfunction "1_AK1") (pintype "bidirectional"))
    )
    (net (code "136") (name "~{MD01}") (class "Default")
      (node (ref "IC1") (pin "11") (pinfunction "O_11") (pintype "output"))
      (node (ref "IC8") (pin "8") (pinfunction "A4_8") (pintype "input"))
      (node (ref "U$2") (pin "AL1") (pinfunction "1_AL1") (pintype "bidirectional"))
    )
    (net (code "137") (name "~{MD02}") (class "Default")
      (node (ref "IC1") (pin "6") (pinfunction "O_6") (pintype "output"))
      (node (ref "IC8") (pin "13") (pinfunction "A2_13") (pintype "input"))
      (node (ref "U$2") (pin "AM1") (pinfunction "1_AM1") (pintype "bidirectional"))
    )
    (net (code "138") (name "~{MD03}") (class "Default")
      (node (ref "IC1") (pin "8") (pinfunction "O_8") (pintype "output"))
      (node (ref "IC8") (pin "6") (pinfunction "A3_6") (pintype "input"))
      (node (ref "U$2") (pin "AP1") (pinfunction "1_AP1") (pintype "bidirectional"))
    )
    (net (code "139") (name "~{MD04}") (class "Default")
      (node (ref "IC2") (pin "3") (pinfunction "O_3") (pintype "output"))
      (node (ref "IC8") (pin "15") (pinfunction "A3_15") (pintype "input"))
      (node (ref "U$2") (pin "BK1") (pinfunction "1_BK1") (pintype "bidirectional"))
    )
    (net (code "140") (name "~{MD05}") (class "Default")
      (node (ref "IC2") (pin "11") (pinfunction "O_11") (pintype "output"))
      (node (ref "IC8") (pin "4") (pinfunction "A2_4") (pintype "input"))
      (node (ref "U$2") (pin "BL1") (pinfunction "1_BL1") (pintype "bidirectional"))
    )
    (net (code "141") (name "~{MD06}") (class "Default")
      (node (ref "IC2") (pin "6") (pinfunction "O_6") (pintype "output"))
      (node (ref "IC8") (pin "17") (pinfunction "A4_17") (pintype "input"))
      (node (ref "U$2") (pin "BM1") (pinfunction "1_BM1") (pintype "bidirectional"))
    )
    (net (code "142") (name "~{MD07}") (class "Default")
      (node (ref "IC2") (pin "8") (pinfunction "O_8") (pintype "output"))
      (node (ref "IC8") (pin "2") (pinfunction "A1_2") (pintype "input"))
      (node (ref "U$2") (pin "BP1") (pinfunction "1_BP1") (pintype "bidirectional"))
    )
    (net (code "143") (name "~{MD08}") (class "Default")
      (node (ref "IC3") (pin "3") (pinfunction "O_3") (pintype "output"))
      (node (ref "IC5") (pin "11") (pinfunction "A1_11") (pintype "input"))
      (node (ref "U$2") (pin "DK1") (pinfunction "1_DK1") (pintype "bidirectional"))
    )
    (net (code "144") (name "~{MD09}") (class "Default")
      (node (ref "IC3") (pin "11") (pinfunction "O_11") (pintype "output"))
      (node (ref "IC5") (pin "13") (pinfunction "A2_13") (pintype "input"))
      (node (ref "U$2") (pin "DL1") (pinfunction "1_DL1") (pintype "bidirectional"))
    )
    (net (code "145") (name "~{MD10}") (class "Default")
      (node (ref "IC3") (pin "6") (pinfunction "O_6") (pintype "output"))
      (node (ref "IC5") (pin "15") (pinfunction "A3_15") (pintype "input"))
      (node (ref "U$2") (pin "DM1") (pinfunction "1_DM1") (pintype "bidirectional"))
    )
    (net (code "146") (name "~{MD11}") (class "Default")
      (node (ref "IC3") (pin "8") (pinfunction "O_8") (pintype "output"))
      (node (ref "IC5") (pin "17") (pinfunction "A4_17") (pintype "input"))
      (node (ref "U$2") (pin "DP1") (pinfunction "1_DP1") (pintype "bidirectional"))
    )
    (net (code "147") (name "~{MD_DIR}") (class "Default")
      (node (ref "IC1") (pin "1") (pinfunction "OE_1") (pintype "input"))
      (node (ref "IC1") (pin "10") (pinfunction "OE_10") (pintype "input"))
      (node (ref "IC1") (pin "13") (pinfunction "OE_13") (pintype "input"))
      (node (ref "IC1") (pin "4") (pinfunction "OE_4") (pintype "input"))
      (node (ref "IC2") (pin "1") (pinfunction "OE_1") (pintype "input"))
      (node (ref "IC2") (pin "10") (pinfunction "OE_10") (pintype "input"))
      (node (ref "IC2") (pin "13") (pinfunction "OE_13") (pintype "input"))
      (node (ref "IC2") (pin "4") (pinfunction "OE_4") (pintype "input"))
      (node (ref "IC3") (pin "1") (pinfunction "OE_1") (pintype "input"))
      (node (ref "IC3") (pin "10") (pinfunction "OE_10") (pintype "input"))
      (node (ref "IC3") (pin "13") (pinfunction "OE_13") (pintype "input"))
      (node (ref "IC3") (pin "4") (pinfunction "OE_4") (pintype "input"))
      (node (ref "U$2") (pin "AK2") (pinfunction "1_AK2") (pintype "bidirectional"))
    )
    (net (code "148") (name "~{MEM_START}") (class "Default")
      (node (ref "U$2") (pin "AJ2") (pinfunction "1_AJ2") (pintype "bidirectional"))
    )
    (net (code "149") (name "~{MS_DISABLE}") (class "Default")
      (node (ref "U$2") (pin "CV1") (pinfunction "1_CV1") (pintype "bidirectional"))
    )
    (net (code "150") (name "~{NOT_LAST_TR}") (class "Default")
      (node (ref "U$2") (pin "CM1") (pinfunction "1_CM1") (pintype "bidirectional"))
    )
    (net (code "151") (name "~{NTS_STALL}") (class "Default")
      (node (ref "U$2") (pin "BR2") (pinfunction "1_BR2") (pintype "bidirectional"))
    )
    (net (code "152") (name "~{OVERFLOW}") (class "Default")
      (node (ref "U$2") (pin "BJ2") (pinfunction "1_BJ2") (pintype "bidirectional"))
    )
    (net (code "153") (name "~{ROM_ADDR}") (class "Default")
      (node (ref "U$2") (pin "AU2") (pinfunction "1_AU2") (pintype "bidirectional"))
    )
    (net (code "154") (name "~{RUN}") (class "Default")
      (node (ref "U$2") (pin "BU2") (pinfunction "1_BU2") (pintype "bidirectional"))
    )
    (net (code "155") (name "~{SKIP}") (class "Default")
      (node (ref "U$2") (pin "CS1") (pinfunction "1_CS1") (pintype "bidirectional"))
    )
    (net (code "156") (name "~{STOP}") (class "Default")
      (node (ref "U$2") (pin "DS2") (pinfunction "1_DS2") (pintype "bidirectional"))
    )
    (net (code "157") (name "~{STROBE}") (class "Default")
      (node (ref "H05") (pin "24") (pinfunction "24_24") (pintype "passive"))
    )
    (net (code "158") (name "~{TS1}") (class "Default")
      (node (ref "U$2") (pin "CK2") (pinfunction "1_CK2") (pintype "bidirectional"))
    )
    (net (code "159") (name "~{TS2}") (class "Default")
      (node (ref "U$2") (pin "CL2") (pinfunction "1_CL2") (pintype "bidirectional"))
    )
    (net (code "160") (name "~{TS3}") (class "Default")
      (node (ref "U$2") (pin "CM2") (pinfunction "1_CM2") (pintype "bidirectional"))
    )
    (net (code "161") (name "~{TS4}") (class "Default")
      (node (ref "U$2") (pin "CP2") (pinfunction "1_CP2") (pintype "bidirectional"))
    )
    (net (code "162") (name "~{USER_MODE}") (class "Default")
      (node (ref "U$2") (pin "DM2") (pinfunction "1_DM2") (pintype "bidirectional"))
    )
  )
)
